# Codec.net
KiCad netlist of a schematic drawn in Altium Designer
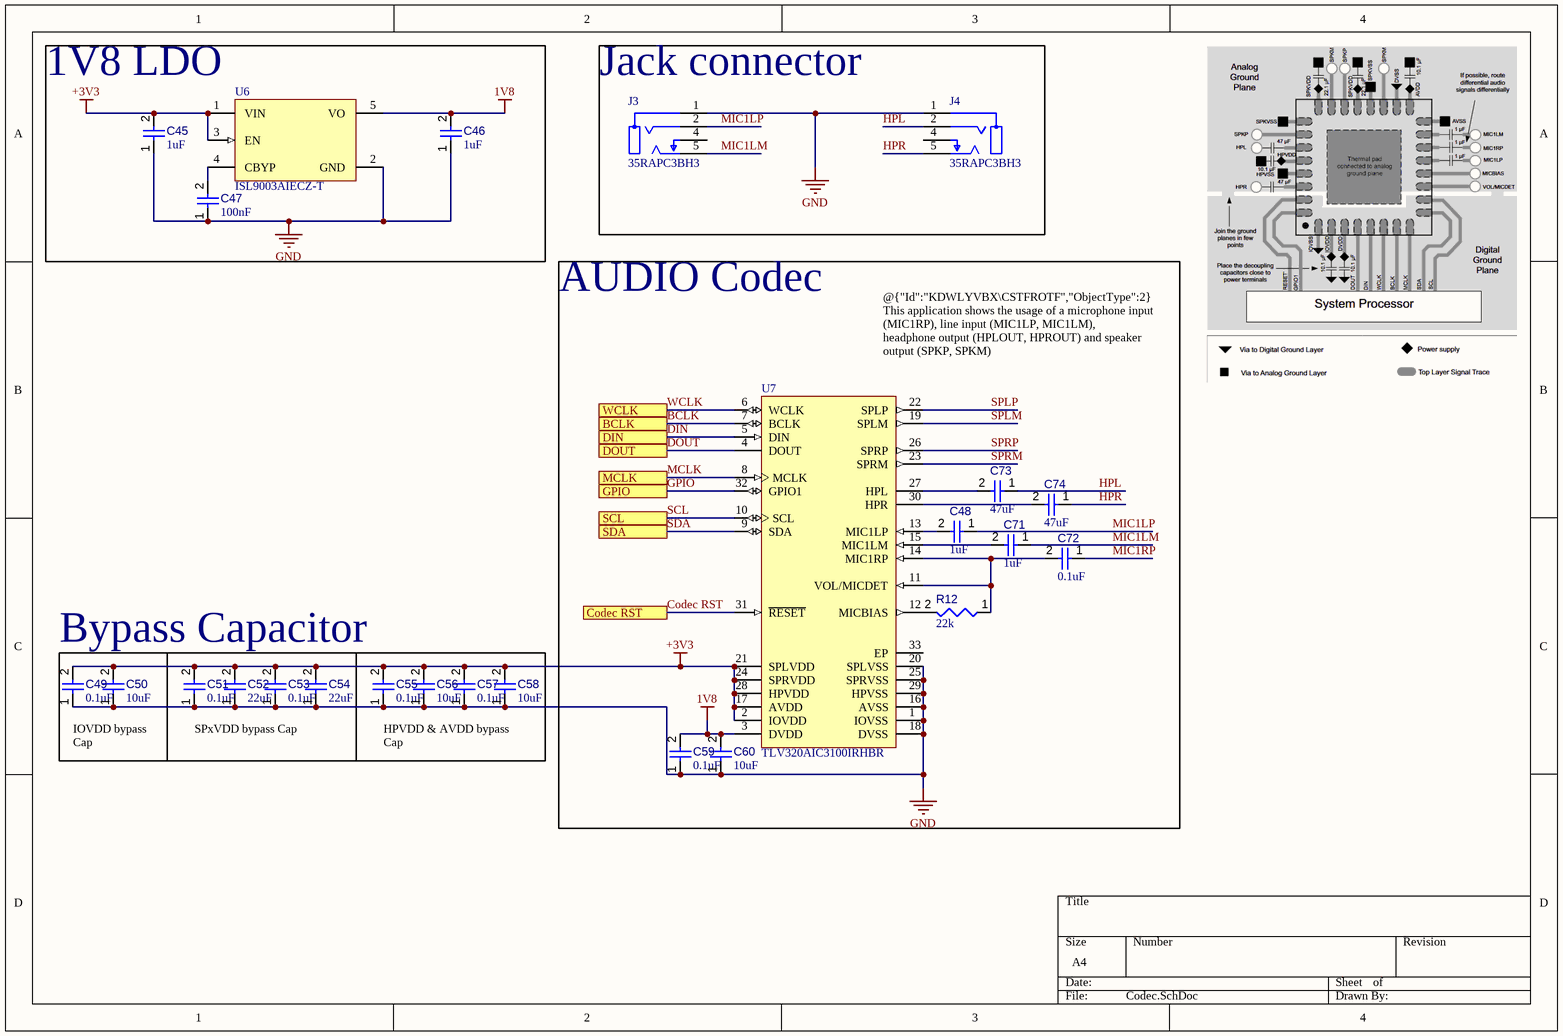
[diagram p0: Codec.SchDoc]

(export (version "E")
  (design (tool "Eeschema 10.0.6"))
  (components
    (comp (ref "C45")
      (value "1uF")
      (footprint "CAPC0603(1608)100_L")
      (description "Chip Capacitor, 470nF +/-20%, 25V, 0603, Thickness 1 mm")
      (fields (field (name "TOLERANCE") "10%") (field (name "Comment") "Capacitor 470nF +/-20% 25V 0603"))
      (libsource (lib "ESD320") (part "CAP-NP-2"))
    )
    (comp (ref "C46")
      (value "1uF")
      (footprint "CAPC0603(1608)100_L")
      (description "Chip Capacitor, 470nF +/-20%, 25V, 0603, Thickness 1 mm")
      (fields (field (name "TOLERANCE") "10%") (field (name "Comment") "Capacitor 470nF +/-20% 25V 0603"))
      (libsource (lib "ESD320") (part "CAP-NP-2"))
    )
    (comp (ref "C47")
      (value "100nF")
      (footprint "CAPC0603(1608)100_L")
      (description "Chip Capacitor, 470nF +/-20%, 25V, 0603, Thickness 1 mm")
      (fields (field (name "TOLERANCE") "10%") (field (name "Comment") "Capacitor 470nF +/-20% 25V 0603"))
      (libsource (lib "ESD320") (part "CAP-NP-2"))
    )
    (comp (ref "C48")
      (value "1uF")
      (footprint "CAPC0603(1608)100_L")
      (description "Chip Capacitor, 470nF +/-20%, 25V, 0603, Thickness 1 mm")
      (fields (field (name "TOLERANCE") "10%") (field (name "Comment") "Capacitor 470nF +/-20% 25V 0603"))
      (libsource (lib "ESD320") (part "CAP-NP-2"))
    )
    (comp (ref "C49")
      (value "0.1uF")
      (footprint "CAPC0603(1608)100_L")
      (description "Chip Capacitor, 470nF +/-20%, 25V, 0603, Thickness 1 mm")
      (fields (field (name "TOLERANCE") "10%") (field (name "Comment") "Capacitor 470nF +/-20% 25V 0603"))
      (libsource (lib "ESD320") (part "CAP-NP-2"))
    )
    (comp (ref "C50")
      (value "10uF")
      (footprint "CAPC0603(1608)100_L")
      (description "Chip Capacitor, 470nF +/-20%, 25V, 0603, Thickness 1 mm")
      (fields (field (name "TOLERANCE") "10%") (field (name "Comment") "Capacitor 470nF +/-20% 25V 0603"))
      (libsource (lib "ESD320") (part "CAP-NP-2"))
    )
    (comp (ref "C51")
      (value "0.1uF")
      (footprint "CAPC0603(1608)100_L")
      (description "Chip Capacitor, 470nF +/-20%, 25V, 0603, Thickness 1 mm")
      (fields (field (name "TOLERANCE") "10%") (field (name "Comment") "Capacitor 470nF +/-20% 25V 0603"))
      (libsource (lib "ESD320") (part "CAP-NP-2"))
    )
    (comp (ref "C52")
      (value "22uF")
      (footprint "CAPC0603(1608)100_L")
      (description "Chip Capacitor, 470nF +/-20%, 25V, 0603, Thickness 1 mm")
      (fields (field (name "TOLERANCE") "10%") (field (name "Comment") "Capacitor 470nF +/-20% 25V 0603"))
      (libsource (lib "ESD320") (part "CAP-NP-2"))
    )
    (comp (ref "C53")
      (value "0.1uF")
      (footprint "CAPC0603(1608)100_L")
      (description "Chip Capacitor, 470nF +/-20%, 25V, 0603, Thickness 1 mm")
      (fields (field (name "TOLERANCE") "10%") (field (name "Comment") "Capacitor 470nF +/-20% 25V 0603"))
      (libsource (lib "ESD320") (part "CAP-NP-2"))
    )
    (comp (ref "C54")
      (value "22uF")
      (footprint "CAPC0603(1608)100_L")
      (description "Chip Capacitor, 470nF +/-20%, 25V, 0603, Thickness 1 mm")
      (fields (field (name "TOLERANCE") "10%") (field (name "Comment") "Capacitor 470nF +/-20% 25V 0603"))
      (libsource (lib "ESD320") (part "CAP-NP-2"))
    )
    (comp (ref "C55")
      (value "0.1uF")
      (footprint "CAPC0603(1608)100_L")
      (description "Chip Capacitor, 470nF +/-20%, 25V, 0603, Thickness 1 mm")
      (fields (field (name "TOLERANCE") "10%") (field (name "Comment") "Capacitor 470nF +/-20% 25V 0603"))
      (libsource (lib "ESD320") (part "CAP-NP-2"))
    )
    (comp (ref "C56")
      (value "10uF")
      (footprint "CAPC0603(1608)100_L")
      (description "Chip Capacitor, 470nF +/-20%, 25V, 0603, Thickness 1 mm")
      (fields (field (name "TOLERANCE") "10%") (field (name "Comment") "Capacitor 470nF +/-20% 25V 0603"))
      (libsource (lib "ESD320") (part "CAP-NP-2"))
    )
    (comp (ref "C57")
      (value "0.1uF")
      (footprint "CAPC0603(1608)100_L")
      (description "Chip Capacitor, 470nF +/-20%, 25V, 0603, Thickness 1 mm")
      (fields (field (name "TOLERANCE") "10%") (field (name "Comment") "Capacitor 470nF +/-20% 25V 0603"))
      (libsource (lib "ESD320") (part "CAP-NP-2"))
    )
    (comp (ref "C58")
      (value "10uF")
      (footprint "CAPC0603(1608)100_L")
      (description "Chip Capacitor, 470nF +/-20%, 25V, 0603, Thickness 1 mm")
      (fields (field (name "TOLERANCE") "10%") (field (name "Comment") "Capacitor 470nF +/-20% 25V 0603"))
      (libsource (lib "ESD320") (part "CAP-NP-2"))
    )
    (comp (ref "C59")
      (value "0.1uF")
      (footprint "CAPC0603(1608)100_L")
      (description "Chip Capacitor, 470nF +/-20%, 25V, 0603, Thickness 1 mm")
      (fields (field (name "TOLERANCE") "10%") (field (name "Comment") "Capacitor 470nF +/-20% 25V 0603"))
      (libsource (lib "ESD320") (part "CAP-NP-2"))
    )
    (comp (ref "C60")
      (value "10uF")
      (footprint "CAPC0603(1608)100_L")
      (description "Chip Capacitor, 470nF +/-20%, 25V, 0603, Thickness 1 mm")
      (fields (field (name "TOLERANCE") "10%") (field (name "Comment") "Capacitor 470nF +/-20% 25V 0603"))
      (libsource (lib "ESD320") (part "CAP-NP-2"))
    )
    (comp (ref "C71")
      (value "1uF")
      (footprint "CAPC0603(1608)100_L")
      (description "Chip Capacitor, 470nF +/-20%, 25V, 0603, Thickness 1 mm")
      (fields (field (name "TOLERANCE") "10%") (field (name "Comment") "Capacitor 470nF +/-20% 25V 0603"))
      (libsource (lib "ESD320") (part "CAP-NP-2"))
    )
    (comp (ref "C72")
      (value "0.1uF")
      (footprint "CAPC0603(1608)100_L")
      (description "Chip Capacitor, 470nF +/-20%, 25V, 0603, Thickness 1 mm")
      (fields (field (name "TOLERANCE") "10%") (field (name "Comment") "Capacitor 470nF +/-20% 25V 0603"))
      (libsource (lib "ESD320") (part "CAP-NP-2"))
    )
    (comp (ref "C73")
      (value "47uF")
      (footprint "CAPC0603(1608)100_L")
      (description "Chip Capacitor, 470nF +/-20%, 25V, 0603, Thickness 1 mm")
      (fields (field (name "TOLERANCE") "10%") (field (name "Comment") "Capacitor 470nF +/-20% 25V 0603"))
      (libsource (lib "ESD320") (part "CAP-NP-2"))
    )
    (comp (ref "C74")
      (value "47uF")
      (footprint "CAPC0603(1608)100_L")
      (description "Chip Capacitor, 470nF +/-20%, 25V, 0603, Thickness 1 mm")
      (fields (field (name "TOLERANCE") "10%") (field (name "Comment") "Capacitor 470nF +/-20% 25V 0603"))
      (libsource (lib "ESD320") (part "CAP-NP-2"))
    )
    (comp (ref "J3")
      (value "35RAPC3BH3")
      (footprint "FP-35RAPC3BH3-MFG")
      (description "CONN JACK STEREO 3.5MM R/A")
      (libsource (lib "Altium Content Vault") (part "6593a1246df2d7246a2ad7da18ee256"))
    )
    (comp (ref "J4")
      (value "35RAPC3BH3")
      (footprint "FP-35RAPC3BH3-MFG")
      (description "CONN JACK STEREO 3.5MM R/A")
      (libsource (lib "Altium Content Vault") (part "6593a1246df2d7246a2ad7da18ee256"))
    )
    (comp (ref "R12")
      (value "22k")
      (footprint "RESC0603(1608)_L")
      (description "120R 0.1W 5% 0603 (1608 Metric)  SMD")
      (fields (field (name "POWER") "100mW") (field (name "TOLERANCE") "5%"))
      (libsource (lib "ESD320") (part "120R3J"))
    )
    (comp (ref "U6")
      (value "ISL9003AIECZ-T")
      (footprint "P5_049_MFG")
      (description "Active Positive GULL WING Not Qualified Linear Voltage Regulator IC 90dB 85C 150mA 2mm")
      (libsource (lib "Altium Content Vault") (part "44bf558302d20fd97f012339b9d58d9"))
    )
    (comp (ref "U7")
      (value "TLV320AIC3100IRHBR")
      (footprint "RHB0032E_V")
      (fields (field (name "MANUFACTURER") "Texas Instruments"))
      (libsource (lib "Altium Content Vault") (part "TI-TLV320AIC3100RHB32-3450X3450TP"))
    )
  )
  (nets
    (net (code "1") (name "+3V3") (class "Default")
      (node (ref "C45") (pin "2") (pinfunction "2_2") (pintype "passive"))
      (node (ref "C49") (pin "2") (pinfunction "2_2") (pintype "passive"))
      (node (ref "C50") (pin "2") (pinfunction "2_2") (pintype "passive"))
      (node (ref "C51") (pin "2") (pinfunction "2_2") (pintype "passive"))
      (node (ref "C52") (pin "2") (pinfunction "2_2") (pintype "passive"))
      (node (ref "C53") (pin "2") (pinfunction "2_2") (pintype "passive"))
      (node (ref "C54") (pin "2") (pinfunction "2_2") (pintype "passive"))
      (node (ref "C55") (pin "2") (pinfunction "2_2") (pintype "passive"))
      (node (ref "C56") (pin "2") (pinfunction "2_2") (pintype "passive"))
      (node (ref "C57") (pin "2") (pinfunction "2_2") (pintype "passive"))
      (node (ref "C58") (pin "2") (pinfunction "2_2") (pintype "passive"))
      (node (ref "U6") (pin "1") (pinfunction "VIN_1") (pintype "power_in"))
      (node (ref "U6") (pin "3") (pinfunction "EN_3") (pintype "input"))
      (node (ref "U7") (pin "17") (pinfunction "AVDD_17") (pintype "power_in"))
      (node (ref "U7") (pin "2") (pinfunction "IOVDD_2") (pintype "power_in"))
      (node (ref "U7") (pin "21") (pinfunction "SPLVDD_21") (pintype "power_in"))
      (node (ref "U7") (pin "24") (pinfunction "SPRVDD_24") (pintype "power_in"))
      (node (ref "U7") (pin "28") (pinfunction "HPVDD_28") (pintype "power_in"))
    )
    (net (code "2") (name "/BCLK") (class "Default")
      (node (ref "U7") (pin "7") (pinfunction "BCLK_7") (pintype "bidirectional"))
    )
    (net (code "3") (name "/Codec RST") (class "Default")
      (node (ref "U7") (pin "31") (pinfunction "~{RESET}_31") (pintype "input"))
    )
    (net (code "4") (name "/DIN") (class "Default")
      (node (ref "U7") (pin "5") (pinfunction "DIN_5") (pintype "input"))
    )
    (net (code "5") (name "/DOUT") (class "Default")
      (node (ref "U7") (pin "4") (pinfunction "DOUT_4") (pintype "tri_state"))
    )
    (net (code "6") (name "/GPIO") (class "Default")
      (node (ref "U7") (pin "32") (pinfunction "GPIO1_32") (pintype "bidirectional"))
    )
    (net (code "7") (name "/HPL") (class "Default")
      (node (ref "C73") (pin "1") (pinfunction "1_1") (pintype "passive"))
      (node (ref "J4") (pin "2") (pinfunction "2_2") (pintype "passive"))
    )
    (net (code "8") (name "/HPR") (class "Default")
      (node (ref "C74") (pin "1") (pinfunction "1_1") (pintype "passive"))
      (node (ref "J4") (pin "5") (pinfunction "5_5") (pintype "passive"))
    )
    (net (code "9") (name "/MCLK") (class "Default")
      (node (ref "U7") (pin "8") (pinfunction "MCLK_8") (pintype "input"))
    )
    (net (code "10") (name "/MIC1LM") (class "Default")
      (node (ref "C71") (pin "1") (pinfunction "1_1") (pintype "passive"))
      (node (ref "J3") (pin "5") (pinfunction "5_5") (pintype "passive"))
    )
    (net (code "11") (name "/MIC1LP") (class "Default")
      (node (ref "C48") (pin "1") (pinfunction "1_1") (pintype "passive"))
      (node (ref "J3") (pin "2") (pinfunction "2_2") (pintype "passive"))
    )
    (net (code "12") (name "/MIC1RP") (class "Default")
      (node (ref "C72") (pin "1") (pinfunction "1_1") (pintype "passive"))
    )
    (net (code "13") (name "/SCL") (class "Default")
      (node (ref "U7") (pin "10") (pinfunction "SCL_10") (pintype "bidirectional"))
    )
    (net (code "14") (name "/SDA") (class "Default")
      (node (ref "U7") (pin "9") (pinfunction "SDA_9") (pintype "bidirectional"))
    )
    (net (code "15") (name "/SPLM") (class "Default")
      (node (ref "U7") (pin "19") (pinfunction "SPLM_19") (pintype "output"))
    )
    (net (code "16") (name "/SPLP") (class "Default")
      (node (ref "U7") (pin "22") (pinfunction "SPLP_22") (pintype "output"))
    )
    (net (code "17") (name "/SPRM") (class "Default")
      (node (ref "U7") (pin "23") (pinfunction "SPRM_23") (pintype "output"))
    )
    (net (code "18") (name "/SPRP") (class "Default")
      (node (ref "U7") (pin "26") (pinfunction "SPRP_26") (pintype "output"))
    )
    (net (code "19") (name "/WCLK") (class "Default")
      (node (ref "U7") (pin "6") (pinfunction "WCLK_6") (pintype "bidirectional"))
    )
    (net (code "20") (name "1V8") (class "Default")
      (node (ref "C46") (pin "2") (pinfunction "2_2") (pintype "passive"))
      (node (ref "C59") (pin "2") (pinfunction "2_2") (pintype "passive"))
      (node (ref "C60") (pin "2") (pinfunction "2_2") (pintype "passive"))
      (node (ref "U6") (pin "5") (pinfunction "VO_5") (pintype "passive"))
      (node (ref "U7") (pin "3") (pinfunction "DVDD_3") (pintype "power_in"))
    )
    (net (code "21") (name "GND") (class "Default")
      (node (ref "C45") (pin "1") (pinfunction "1_1") (pintype "passive"))
      (node (ref "C46") (pin "1") (pinfunction "1_1") (pintype "passive"))
      (node (ref "C47") (pin "1") (pinfunction "1_1") (pintype "passive"))
      (node (ref "C49") (pin "1") (pinfunction "1_1") (pintype "passive"))
      (node (ref "C50") (pin "1") (pinfunction "1_1") (pintype "passive"))
      (node (ref "C51") (pin "1") (pinfunction "1_1") (pintype "passive"))
      (node (ref "C52") (pin "1") (pinfunction "1_1") (pintype "passive"))
      (node (ref "C53") (pin "1") (pinfunction "1_1") (pintype "passive"))
      (node (ref "C54") (pin "1") (pinfunction "1_1") (pintype "passive"))
      (node (ref "C55") (pin "1") (pinfunction "1_1") (pintype "passive"))
      (node (ref "C56") (pin "1") (pinfunction "1_1") (pintype "passive"))
      (node (ref "C57") (pin "1") (pinfunction "1_1") (pintype "passive"))
      (node (ref "C58") (pin "1") (pinfunction "1_1") (pintype "passive"))
      (node (ref "C59") (pin "1") (pinfunction "1_1") (pintype "passive"))
      (node (ref "C60") (pin "1") (pinfunction "1_1") (pintype "passive"))
      (node (ref "J3") (pin "1") (pinfunction "1_1") (pintype "passive"))
      (node (ref "J4") (pin "1") (pinfunction "1_1") (pintype "passive"))
      (node (ref "U6") (pin "2") (pinfunction "GND_2") (pintype "power_in"))
      (node (ref "U7") (pin "1") (pinfunction "IOVSS_1") (pintype "power_in"))
      (node (ref "U7") (pin "16") (pinfunction "AVSS_16") (pintype "power_in"))
      (node (ref "U7") (pin "18") (pinfunction "DVSS_18") (pintype "power_in"))
      (node (ref "U7") (pin "20") (pinfunction "SPLVSS_20") (pintype "power_in"))
      (node (ref "U7") (pin "25") (pinfunction "SPRVSS_25") (pintype "power_in"))
      (node (ref "U7") (pin "29") (pinfunction "HPVSS_29") (pintype "power_in"))
    )
    (net (code "22") (name "Net-(U6-CBYP)") (class "Default")
      (node (ref "C47") (pin "2") (pinfunction "2_2") (pintype "passive"))
      (node (ref "U6") (pin "4") (pinfunction "CBYP_4") (pintype "passive"))
    )
    (net (code "23") (name "Net-(U7-HPL)") (class "Default")
      (node (ref "C73") (pin "2") (pinfunction "2_2") (pintype "passive"))
      (node (ref "U7") (pin "27") (pinfunction "HPL_27") (pintype "tri_state"))
    )
    (net (code "24") (name "Net-(U7-HPR)") (class "Default")
      (node (ref "C74") (pin "2") (pinfunction "2_2") (pintype "passive"))
      (node (ref "U7") (pin "30") (pinfunction "HPR_30") (pintype "tri_state"))
    )
    (net (code "25") (name "Net-(U7-MIC1LM)") (class "Default")
      (node (ref "C71") (pin "2") (pinfunction "2_2") (pintype "passive"))
      (node (ref "U7") (pin "15") (pinfunction "MIC1LM_15") (pintype "input"))
    )
    (net (code "26") (name "Net-(U7-MIC1LP)") (class "Default")
      (node (ref "C48") (pin "2") (pinfunction "2_2") (pintype "passive"))
      (node (ref "U7") (pin "13") (pinfunction "MIC1LP_13") (pintype "input"))
    )
    (net (code "27") (name "Net-(U7-MIC1RP)") (class "Default")
      (node (ref "C72") (pin "2") (pinfunction "2_2") (pintype "passive"))
      (node (ref "R12") (pin "1") (pinfunction "1_1") (pintype "passive"))
      (node (ref "U7") (pin "11") (pinfunction "VOL/MICDET_11") (pintype "input"))
      (node (ref "U7") (pin "14") (pinfunction "MIC1RP_14") (pintype "input"))
    )
    (net (code "28") (name "Net-(U7-MICBIAS)") (class "Default")
      (node (ref "R12") (pin "2") (pinfunction "2_2") (pintype "passive"))
      (node (ref "U7") (pin "12") (pinfunction "MICBIAS_12") (pintype "output"))
    )
    (net (code "29") (name "unconnected-(J3-Pad4)") (class "Default")
      (node (ref "J3") (pin "4") (pinfunction "4_4") (pintype "passive"))
    )
    (net (code "30") (name "unconnected-(J4-Pad4)") (class "Default")
      (node (ref "J4") (pin "4") (pinfunction "4_4") (pintype "passive"))
    )
    (net (code "31") (name "unconnected-(U7-EP-Pad33)") (class "Default")
      (node (ref "U7") (pin "33") (pinfunction "EP_33") (pintype "passive"))
    )
  )
)
